# relay.net
KiCad netlist of a schematic drawn in Altium Designer
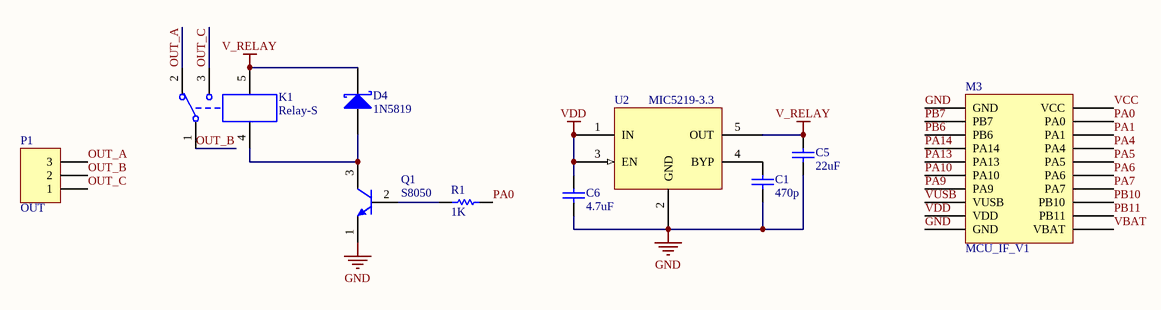
[diagram p0: relay.SchDoc]

(export (version "E")
  (design (tool "Eeschema 10.0.6"))
  (components
    (comp (ref "C1")
      (value "470p")
      (footprint "C-1608[0603]")
      (description "Capacitor (Semiconductor SIM Model)")
      (fields (field (name "Comment") "Cap Semi") (field (name "PUBLISHER") "Altium Limited"))
      (libsource (lib "Miscellaneous Devices") (part "Cap Semi"))
    )
    (comp (ref "C5")
      (value "22uF")
      (footprint "C-2012[0805]")
      (description "Capacitor (Semiconductor SIM Model)")
      (fields (field (name "Comment") "Cap Semi") (field (name "PUBLISHER") "Altium Limited"))
      (libsource (lib "Miscellaneous Devices") (part "Cap Semi"))
    )
    (comp (ref "C6")
      (value "4.7uF")
      (footprint "C-1608[0603]")
      (description "Capacitor (Semiconductor SIM Model)")
      (fields (field (name "Comment") "Cap Semi") (field (name "PUBLISHER") "Altium Limited"))
      (libsource (lib "Miscellaneous Devices") (part "Cap Semi"))
    )
    (comp (ref "D4")
      (value "1N5819")
      (footprint "PcbLib1:SOD123")
      (description "Schottky Diode")
      (fields (field (name "PUBLISHER") "Altium Limited"))
      (libsource (lib "Miscellaneous Devices") (part "D Schottky"))
    )
    (comp (ref "K1")
      (value "Relay-S")
      (footprint "Relay-JZC-32F-ZS")
      (description "Single-Pole Dual-Throw Relay")
      (fields (field (name "PUBLISHER") "Altium Limited"))
      (libsource (lib "Miscellaneous Devices") (part "Relay-SPDT"))
    )
    (comp (ref "M3")
      (value "MCU_IF_V1")
      (footprint "MCU_IF_V1")
      (libsource (lib "MCU_IF") (part "MCU_IF_V1"))
    )
    (comp (ref "P1")
      (value "OUT")
      (footprint "Edge5.08mm3P")
      (description "Header, 3-Pin")
      (fields (field (name "PUBLISHER") "Altium Limited"))
      (libsource (lib "Miscellaneous Connectors") (part "Header 3"))
    )
    (comp (ref "Q1")
      (value "S8050")
      (footprint "SOT23B")
      (description "NPN General Purpose Amplifier")
      (fields (field (name "PUBLISHER") "Altium Limited"))
      (libsource (lib "Miscellaneous Devices") (part "2N3904"))
    )
    (comp (ref "R1")
      (value "1K")
      (footprint "R-1608[0603]")
      (description "Semiconductor Resistor")
      (fields (field (name "Comment") "Res Semi") (field (name "PUBLISHER") "Altium Limited"))
      (libsource (lib "Miscellaneous Devices") (part "Res Semi"))
    )
    (comp (ref "U2")
      (value "MIC5219-3.3")
      (footprint "SOT23-5")
      (description "500mA-Peak Output LDO Regulator")
      (libsource (lib "Schlib1") (part "MIC5219"))
    )
  )
  (nets
    (net (code "1") (name "/OUT_A") (class "Default")
      (node (ref "K1") (pin "2") (pinfunction "2_2") (pintype "passive"))
      (node (ref "P1") (pin "3") (pinfunction "3_3") (pintype "passive"))
    )
    (net (code "2") (name "/OUT_B") (class "Default")
      (node (ref "K1") (pin "1") (pinfunction "1_1") (pintype "passive"))
      (node (ref "P1") (pin "2") (pinfunction "2_2") (pintype "passive"))
    )
    (net (code "3") (name "/OUT_C") (class "Default")
      (node (ref "K1") (pin "3") (pinfunction "3_3") (pintype "passive"))
      (node (ref "P1") (pin "1") (pinfunction "1_1") (pintype "passive"))
    )
    (net (code "4") (name "/PA0") (class "Default")
      (node (ref "M3") (pin "19") (pinfunction "PA0_19") (pintype "passive"))
      (node (ref "R1") (pin "2") (pinfunction "2_2") (pintype "passive"))
    )
    (net (code "5") (name "/PA1") (class "Default")
      (node (ref "M3") (pin "18") (pinfunction "PA1_18") (pintype "passive"))
    )
    (net (code "6") (name "/PA4") (class "Default")
      (node (ref "M3") (pin "17") (pinfunction "PA4_17") (pintype "passive"))
    )
    (net (code "7") (name "/PA5") (class "Default")
      (node (ref "M3") (pin "16") (pinfunction "PA5_16") (pintype "passive"))
    )
    (net (code "8") (name "/PA6") (class "Default")
      (node (ref "M3") (pin "15") (pinfunction "PA6_15") (pintype "passive"))
    )
    (net (code "9") (name "/PA7") (class "Default")
      (node (ref "M3") (pin "14") (pinfunction "PA7_14") (pintype "passive"))
    )
    (net (code "10") (name "/PA9") (class "Default")
      (node (ref "M3") (pin "7") (pinfunction "PA9_7") (pintype "passive"))
    )
    (net (code "11") (name "/PA10") (class "Default")
      (node (ref "M3") (pin "6") (pinfunction "PA10_6") (pintype "passive"))
    )
    (net (code "12") (name "/PA13") (class "Default")
      (node (ref "M3") (pin "5") (pinfunction "PA13_5") (pintype "passive"))
    )
    (net (code "13") (name "/PA14") (class "Default")
      (node (ref "M3") (pin "4") (pinfunction "PA14_4") (pintype "passive"))
    )
    (net (code "14") (name "/PB6") (class "Default")
      (node (ref "M3") (pin "3") (pinfunction "PB6_3") (pintype "passive"))
    )
    (net (code "15") (name "/PB7") (class "Default")
      (node (ref "M3") (pin "2") (pinfunction "PB7_2") (pintype "passive"))
    )
    (net (code "16") (name "/PB10") (class "Default")
      (node (ref "M3") (pin "13") (pinfunction "PB10_13") (pintype "passive"))
    )
    (net (code "17") (name "/PB11") (class "Default")
      (node (ref "M3") (pin "12") (pinfunction "PB11_12") (pintype "passive"))
    )
    (net (code "18") (name "/VBAT") (class "Default")
      (node (ref "M3") (pin "11") (pinfunction "VBAT_11") (pintype "passive"))
    )
    (net (code "19") (name "/VCC") (class "Default")
      (node (ref "M3") (pin "20") (pinfunction "VCC_20") (pintype "passive"))
    )
    (net (code "20") (name "/VUSB") (class "Default")
      (node (ref "M3") (pin "8") (pinfunction "VUSB_8") (pintype "passive"))
    )
    (net (code "21") (name "GND") (class "Default")
      (node (ref "C1") (pin "2") (pinfunction "2_2") (pintype "passive"))
      (node (ref "C5") (pin "2") (pinfunction "2_2") (pintype "passive"))
      (node (ref "C6") (pin "2") (pinfunction "2_2") (pintype "passive"))
      (node (ref "M3") (pin "1") (pinfunction "GND_1") (pintype "passive"))
      (node (ref "M3") (pin "10") (pinfunction "GND_10") (pintype "passive"))
      (node (ref "Q1") (pin "1") (pinfunction "E_1") (pintype "passive"))
      (node (ref "U2") (pin "2") (pinfunction "GND_2") (pintype "passive"))
    )
    (net (code "22") (name "Net-(D4-A)") (class "Default")
      (node (ref "D4") (pin "1") (pinfunction "A_1") (pintype "passive"))
      (node (ref "K1") (pin "4") (pinfunction "4_4") (pintype "passive"))
      (node (ref "Q1") (pin "3") (pinfunction "C_3") (pintype "passive"))
    )
    (net (code "23") (name "Net-(Q1-B)") (class "Default")
      (node (ref "Q1") (pin "2") (pinfunction "B_2") (pintype "passive"))
      (node (ref "R1") (pin "1") (pinfunction "1_1") (pintype "passive"))
    )
    (net (code "24") (name "Net-(U2-BYP)") (class "Default")
      (node (ref "C1") (pin "1") (pinfunction "1_1") (pintype "passive"))
      (node (ref "U2") (pin "4") (pinfunction "BYP_4") (pintype "passive"))
    )
    (net (code "25") (name "VDD") (class "Default")
      (node (ref "C6") (pin "1") (pinfunction "1_1") (pintype "passive"))
      (node (ref "M3") (pin "9") (pinfunction "VDD_9") (pintype "passive"))
      (node (ref "U2") (pin "1") (pinfunction "IN_1") (pintype "power_in"))
      (node (ref "U2") (pin "3") (pinfunction "EN_3") (pintype "input"))
    )
    (net (code "26") (name "V_RELAY") (class "Default")
      (node (ref "C5") (pin "1") (pinfunction "1_1") (pintype "passive"))
      (node (ref "D4") (pin "2") (pinfunction "K_2") (pintype "passive"))
      (node (ref "K1") (pin "5") (pinfunction "5_5") (pintype "passive"))
      (node (ref "U2") (pin "5") (pinfunction "OUT_5") (pintype "passive"))
    )
  )
)
